# electrical_stuff_2_0.net
KiCad netlist of a schematic drawn in EAGLE
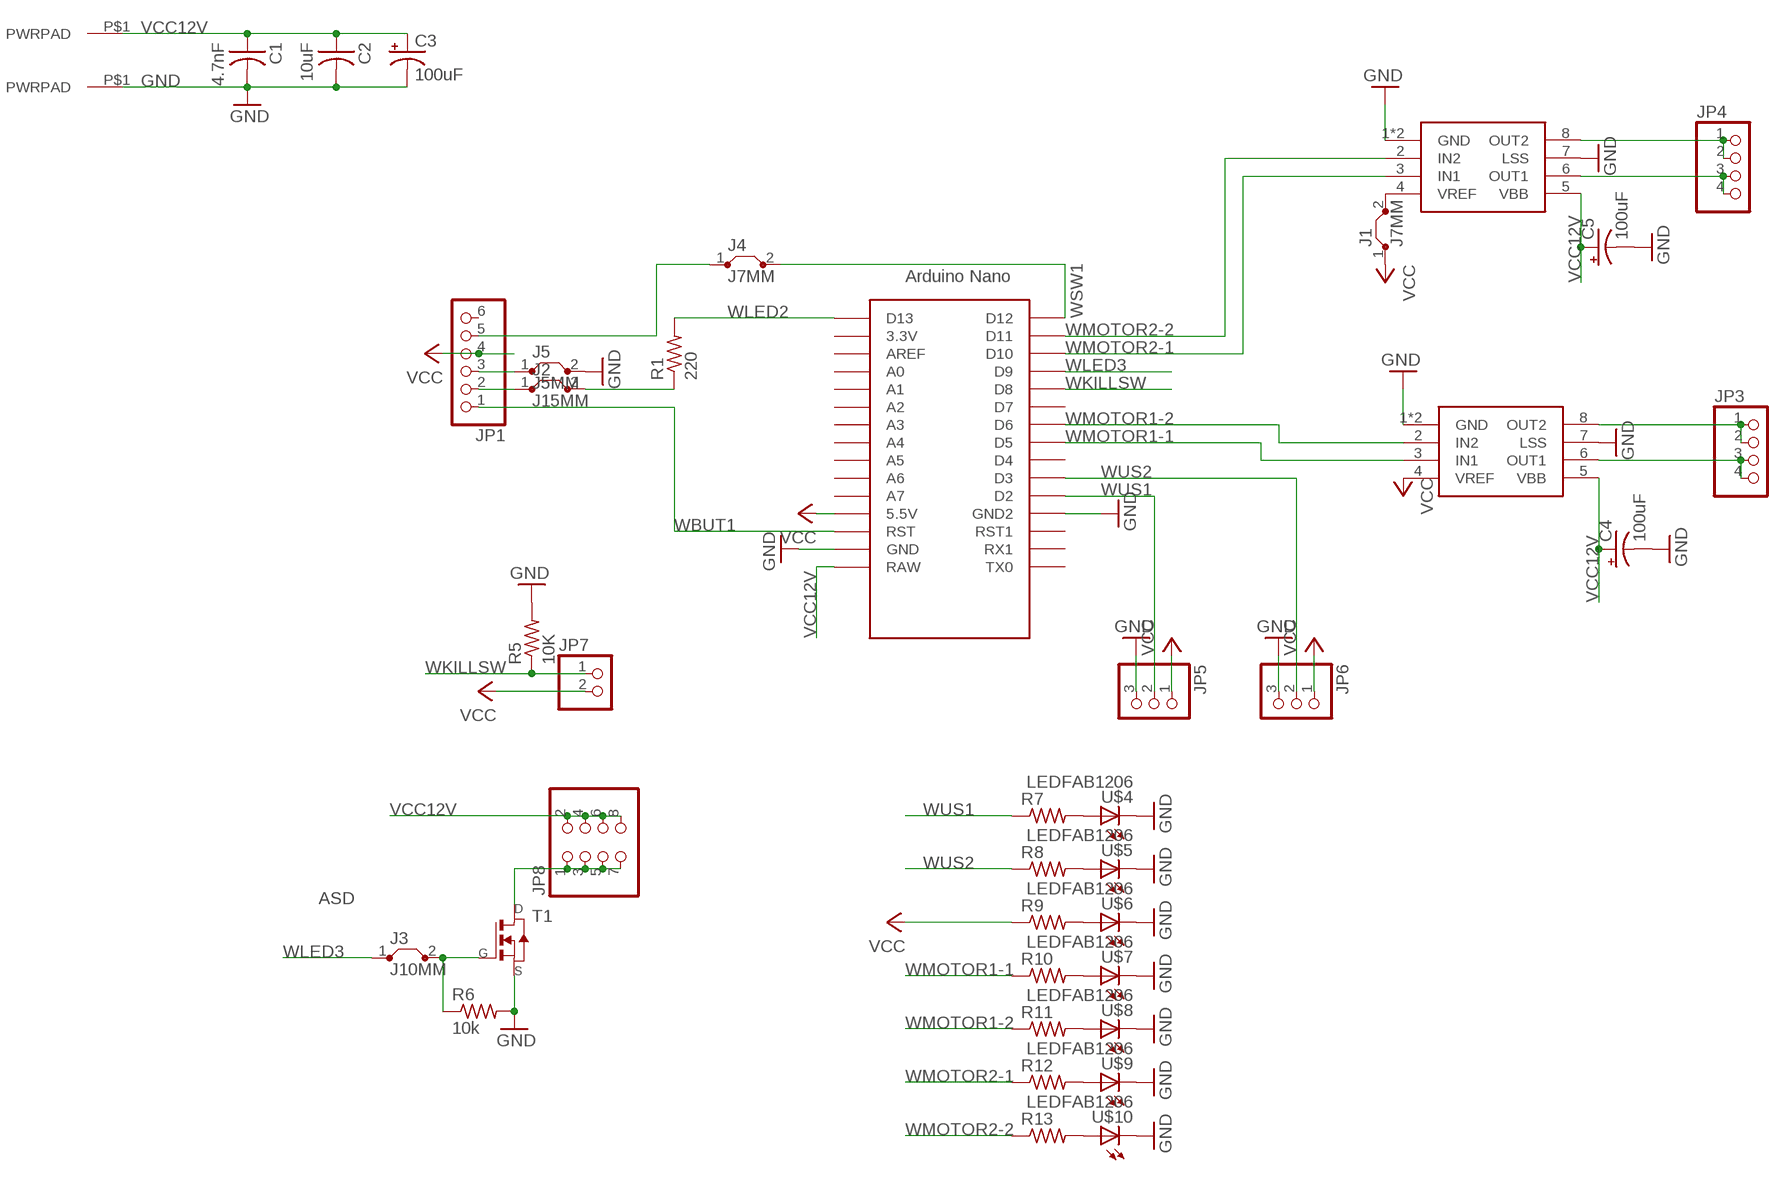
[diagram p0: schematic, sheet 1]

(export (version "E")
  (design (tool "Eeschema 10.0.6"))
  (components
    (comp (ref "C1")
      (value "4.7nF")
      (footprint "eagle-import:C1206FAB")
      (libsource (lib "eagle-import") (part "CAP-US1206FAB"))
    )
    (comp (ref "C2")
      (value "10uF")
      (footprint "eagle-import:C1206FAB")
      (libsource (lib "eagle-import") (part "CAP-US1206FAB"))
    )
    (comp (ref "C3")
      (value "100uF")
      (footprint "eagle-import:CPOL-RADIAL-2.5MM-6.5MM")
      (libsource (lib "eagle-import") (part "100UF-POLAR-RADIAL-2.5MM-25V-20%"))
    )
    (comp (ref "C4")
      (value "100uF")
      (footprint "eagle-import:CPOL-RADIAL-2.5MM-6.5MM")
      (libsource (lib "eagle-import") (part "100UF-POLAR-RADIAL-2.5MM-25V-20%"))
    )
    (comp (ref "C5")
      (value "100uF")
      (footprint "eagle-import:CPOL-RADIAL-2.5MM-6.5MM")
      (libsource (lib "eagle-import") (part "100UF-POLAR-RADIAL-2.5MM-25V-20%"))
    )
    (comp (ref "GND")
      (value "PWRPAD2-5MM")
      (footprint "eagle-import:PWRPAD_2-5MM")
      (libsource (lib "eagle-import") (part "PWRPAD2-5MM"))
    )
    (comp (ref "J1")
      (value "J7MM")
      (footprint "eagle-import:07")
      (libsource (lib "eagle-import") (part "J7MM"))
    )
    (comp (ref "J2")
      (value "J15MM")
      (footprint "eagle-import:15")
      (libsource (lib "eagle-import") (part "J15MM"))
    )
    (comp (ref "J3")
      (value "J10MM")
      (footprint "eagle-import:10")
      (libsource (lib "eagle-import") (part "J10MM"))
    )
    (comp (ref "J4")
      (value "J7MM")
      (footprint "eagle-import:07")
      (libsource (lib "eagle-import") (part "J7MM"))
    )
    (comp (ref "J5")
      (value "J5MM")
      (footprint "eagle-import:05")
      (libsource (lib "eagle-import") (part "J5MM"))
    )
    (comp (ref "JP1")
      (value "PINHD-1X6")
      (footprint "eagle-import:1X06")
      (libsource (lib "eagle-import") (part "PINHD-1X6"))
    )
    (comp (ref "JP3")
      (value "PINHD-1X4")
      (footprint "eagle-import:1X04")
      (libsource (lib "eagle-import") (part "PINHD-1X4"))
    )
    (comp (ref "JP4")
      (value "PINHD-1X4")
      (footprint "eagle-import:1X04")
      (libsource (lib "eagle-import") (part "PINHD-1X4"))
    )
    (comp (ref "JP5")
      (value "PINHD-1X3")
      (footprint "eagle-import:1X03")
      (libsource (lib "eagle-import") (part "PINHD-1X3"))
    )
    (comp (ref "JP6")
      (value "PINHD-1X3")
      (footprint "eagle-import:1X03")
      (libsource (lib "eagle-import") (part "PINHD-1X3"))
    )
    (comp (ref "JP7")
      (value "PINHD-1X2")
      (footprint "eagle-import:1X02")
      (libsource (lib "eagle-import") (part "PINHD-1X2"))
    )
    (comp (ref "JP8")
      (value "PINHD-2X4")
      (footprint "eagle-import:2X04")
      (libsource (lib "eagle-import") (part "PINHD-2X4"))
    )
    (comp (ref "R1")
      (value "220")
      (footprint "eagle-import:R1206FAB")
      (libsource (lib "eagle-import") (part "RES-US1206FAB"))
    )
    (comp (ref "R5")
      (value "10K")
      (footprint "eagle-import:R1206FAB")
      (libsource (lib "eagle-import") (part "RES-US1206FAB"))
    )
    (comp (ref "R6")
      (value "10k")
      (footprint "eagle-import:R1206FAB")
      (libsource (lib "eagle-import") (part "RES-US1206FAB"))
    )
    (comp (ref "R7")
      (value "RES-US1206FAB")
      (footprint "eagle-import:R1206FAB")
      (libsource (lib "eagle-import") (part "RES-US1206FAB"))
    )
    (comp (ref "R8")
      (value "RES-US1206FAB")
      (footprint "eagle-import:R1206FAB")
      (libsource (lib "eagle-import") (part "RES-US1206FAB"))
    )
    (comp (ref "R9")
      (value "RES-US1206FAB")
      (footprint "eagle-import:R1206FAB")
      (libsource (lib "eagle-import") (part "RES-US1206FAB"))
    )
    (comp (ref "R10")
      (value "RES-US1206FAB")
      (footprint "eagle-import:R1206FAB")
      (libsource (lib "eagle-import") (part "RES-US1206FAB"))
    )
    (comp (ref "R11")
      (value "RES-US1206FAB")
      (footprint "eagle-import:R1206FAB")
      (libsource (lib "eagle-import") (part "RES-US1206FAB"))
    )
    (comp (ref "R12")
      (value "RES-US1206FAB")
      (footprint "eagle-import:R1206FAB")
      (libsource (lib "eagle-import") (part "RES-US1206FAB"))
    )
    (comp (ref "R13")
      (value "RES-US1206FAB")
      (footprint "eagle-import:R1206FAB")
      (libsource (lib "eagle-import") (part "RES-US1206FAB"))
    )
    (comp (ref "T1")
      (value "NMOSFETTO252")
      (footprint "eagle-import:TO252")
      (libsource (lib "eagle-import") (part "NMOSFETTO252"))
    )
    (comp (ref "U$1")
      (value "NANO")
      (footprint "eagle-import:NANO")
      (libsource (lib "eagle-import") (part "NANO"))
    )
    (comp (ref "U$2")
      (value "A4953")
      (footprint "eagle-import:SOIC8_PAD")
      (libsource (lib "eagle-import") (part "A4953-H-BRIDGE-MOTOR-DRIVER-PAD"))
    )
    (comp (ref "U$3")
      (value "A4953")
      (footprint "eagle-import:SOIC8_PAD")
      (libsource (lib "eagle-import") (part "A4953-H-BRIDGE-MOTOR-DRIVER-PAD"))
    )
    (comp (ref "U$4")
      (value "LEDFAB1206")
      (footprint "eagle-import:LED1206FAB")
      (libsource (lib "eagle-import") (part "LEDFAB1206"))
    )
    (comp (ref "U$5")
      (value "LEDFAB1206")
      (footprint "eagle-import:LED1206FAB")
      (libsource (lib "eagle-import") (part "LEDFAB1206"))
    )
    (comp (ref "U$6")
      (value "LEDFAB1206")
      (footprint "eagle-import:LED1206FAB")
      (libsource (lib "eagle-import") (part "LEDFAB1206"))
    )
    (comp (ref "U$7")
      (value "LEDFAB1206")
      (footprint "eagle-import:LED1206FAB")
      (libsource (lib "eagle-import") (part "LEDFAB1206"))
    )
    (comp (ref "U$8")
      (value "LEDFAB1206")
      (footprint "eagle-import:LED1206FAB")
      (libsource (lib "eagle-import") (part "LEDFAB1206"))
    )
    (comp (ref "U$9")
      (value "LEDFAB1206")
      (footprint "eagle-import:LED1206FAB")
      (libsource (lib "eagle-import") (part "LEDFAB1206"))
    )
    (comp (ref "U$10")
      (value "LEDFAB1206")
      (footprint "eagle-import:LED1206FAB")
      (libsource (lib "eagle-import") (part "LEDFAB1206"))
    )
    (comp (ref "VCC12V")
      (value "VCC12V")
      (footprint "eagle-import:PWRPAD_2-5MM")
      (libsource (lib "eagle-import") (part "PWRPAD2-5MM"))
    )
  )
  (nets
    (net (code "1") (name "/ASD") (class "Default")
      (node (ref "J3") (pin "2") (pinfunction "2_2") (pintype "passive"))
      (node (ref "R6") (pin "1") (pinfunction "1_1") (pintype "passive"))
      (node (ref "T1") (pin "1") (pinfunction "G_1") (pintype "passive"))
    )
    (net (code "2") (name "/VCC12V") (class "Default")
      (node (ref "C1") (pin "1") (pinfunction "1_1") (pintype "passive"))
      (node (ref "C2") (pin "1") (pinfunction "1_1") (pintype "passive"))
      (node (ref "C3") (pin "1") (pinfunction "+_1") (pintype "passive"))
      (node (ref "C4") (pin "1") (pinfunction "+_1") (pintype "passive"))
      (node (ref "C5") (pin "1") (pinfunction "+_1") (pintype "passive"))
      (node (ref "JP8") (pin "2") (pinfunction "2_2") (pintype "passive"))
      (node (ref "JP8") (pin "4") (pinfunction "4_4") (pintype "passive"))
      (node (ref "JP8") (pin "6") (pinfunction "6_6") (pintype "passive"))
      (node (ref "JP8") (pin "8") (pinfunction "8_8") (pintype "passive"))
      (node (ref "U$1") (pin "RAW") (pinfunction "RAW_RAW") (pintype "bidirectional"))
      (node (ref "U$2") (pin "5") (pinfunction "VBB_5") (pintype "bidirectional"))
      (node (ref "U$3") (pin "5") (pinfunction "VBB_5") (pintype "bidirectional"))
      (node (ref "VCC12V") (pin "P$1") (pinfunction "PWRPAD_P$1") (pintype "bidirectional"))
    )
    (net (code "3") (name "/WBUT1") (class "Default")
      (node (ref "JP1") (pin "1") (pinfunction "1_1") (pintype "passive"))
      (node (ref "U$1") (pin "RST") (pinfunction "RST_RST") (pintype "bidirectional"))
    )
    (net (code "4") (name "/WKILLSW") (class "Default")
      (node (ref "JP7") (pin "1") (pinfunction "1_1") (pintype "passive"))
      (node (ref "R5") (pin "1") (pinfunction "1_1") (pintype "passive"))
      (node (ref "U$1") (pin "D8") (pinfunction "D8_D8") (pintype "bidirectional"))
    )
    (net (code "5") (name "/WLED2") (class "Default")
      (node (ref "R1") (pin "2") (pinfunction "2_2") (pintype "passive"))
      (node (ref "U$1") (pin "D13") (pinfunction "D13_D13") (pintype "bidirectional"))
    )
    (net (code "6") (name "/WLED3") (class "Default")
      (node (ref "J3") (pin "1") (pinfunction "1_1") (pintype "passive"))
      (node (ref "U$1") (pin "D9") (pinfunction "D9_D9") (pintype "bidirectional"))
    )
    (net (code "7") (name "/WMOTOR1-1") (class "Default")
      (node (ref "R10") (pin "1") (pinfunction "1_1") (pintype "passive"))
      (node (ref "U$1") (pin "D5") (pinfunction "D5_D5") (pintype "bidirectional"))
      (node (ref "U$2") (pin "3") (pinfunction "IN1_3") (pintype "bidirectional"))
    )
    (net (code "8") (name "/WMOTOR1-2") (class "Default")
      (node (ref "R11") (pin "1") (pinfunction "1_1") (pintype "passive"))
      (node (ref "U$1") (pin "D6") (pinfunction "D6_D6") (pintype "bidirectional"))
      (node (ref "U$2") (pin "2") (pinfunction "IN2_2") (pintype "bidirectional"))
    )
    (net (code "9") (name "/WMOTOR2-1") (class "Default")
      (node (ref "R12") (pin "1") (pinfunction "1_1") (pintype "passive"))
      (node (ref "U$1") (pin "D10") (pinfunction "D10_D10") (pintype "bidirectional"))
      (node (ref "U$3") (pin "3") (pinfunction "IN1_3") (pintype "bidirectional"))
    )
    (net (code "10") (name "/WMOTOR2-2") (class "Default")
      (node (ref "R13") (pin "1") (pinfunction "1_1") (pintype "passive"))
      (node (ref "U$1") (pin "D11") (pinfunction "D11_D11") (pintype "bidirectional"))
      (node (ref "U$3") (pin "2") (pinfunction "IN2_2") (pintype "bidirectional"))
    )
    (net (code "11") (name "/WSW1") (class "Default")
      (node (ref "J4") (pin "2") (pinfunction "2_2") (pintype "passive"))
      (node (ref "U$1") (pin "D12") (pinfunction "D12_D12") (pintype "bidirectional"))
    )
    (net (code "12") (name "/WUS1") (class "Default")
      (node (ref "JP5") (pin "2") (pinfunction "2_2") (pintype "passive"))
      (node (ref "R7") (pin "1") (pinfunction "1_1") (pintype "passive"))
      (node (ref "U$1") (pin "D2") (pinfunction "D2_D2") (pintype "bidirectional"))
    )
    (net (code "13") (name "/WUS2") (class "Default")
      (node (ref "JP6") (pin "2") (pinfunction "2_2") (pintype "passive"))
      (node (ref "R8") (pin "1") (pinfunction "1_1") (pintype "passive"))
      (node (ref "U$1") (pin "D3") (pinfunction "D3_D3") (pintype "bidirectional"))
    )
    (net (code "14") (name "GND") (class "Default")
      (node (ref "C1") (pin "2") (pinfunction "2_2") (pintype "passive"))
      (node (ref "C2") (pin "2") (pinfunction "2_2") (pintype "passive"))
      (node (ref "C3") (pin "2") (pinfunction "-_2") (pintype "passive"))
      (node (ref "C4") (pin "2") (pinfunction "-_2") (pintype "passive"))
      (node (ref "C5") (pin "2") (pinfunction "-_2") (pintype "passive"))
      (node (ref "GND") (pin "P$1") (pinfunction "PWRPAD_P$1") (pintype "bidirectional"))
      (node (ref "J5") (pin "2") (pinfunction "2_2") (pintype "passive"))
      (node (ref "JP5") (pin "3") (pinfunction "3_3") (pintype "passive"))
      (node (ref "JP6") (pin "3") (pinfunction "3_3") (pintype "passive"))
      (node (ref "R5") (pin "2") (pinfunction "2_2") (pintype "passive"))
      (node (ref "R6") (pin "2") (pinfunction "2_2") (pintype "passive"))
      (node (ref "T1") (pin "2") (pinfunction "S_2") (pintype "passive"))
      (node (ref "U$1") (pin "GND") (pinfunction "GND_GND") (pintype "bidirectional"))
      (node (ref "U$1") (pin "GND1") (pinfunction "GND2_GND1") (pintype "bidirectional"))
      (node (ref "U$10") (pin "2") (pinfunction "C_2") (pintype "passive"))
      (node (ref "U$2") (pin "1") (pinfunction "GND_1") (pintype "bidirectional"))
      (node (ref "U$2") (pin "7") (pinfunction "LSS_7") (pintype "bidirectional"))
      (node (ref "U$2") (pin "GND") (pinfunction "GND_GND") (pintype "bidirectional"))
      (node (ref "U$3") (pin "1") (pinfunction "GND_1") (pintype "bidirectional"))
      (node (ref "U$3") (pin "7") (pinfunction "LSS_7") (pintype "bidirectional"))
      (node (ref "U$3") (pin "GND") (pinfunction "GND_GND") (pintype "bidirectional"))
      (node (ref "U$4") (pin "2") (pinfunction "C_2") (pintype "passive"))
      (node (ref "U$5") (pin "2") (pinfunction "C_2") (pintype "passive"))
      (node (ref "U$6") (pin "2") (pinfunction "C_2") (pintype "passive"))
      (node (ref "U$7") (pin "2") (pinfunction "C_2") (pintype "passive"))
      (node (ref "U$8") (pin "2") (pinfunction "C_2") (pintype "passive"))
      (node (ref "U$9") (pin "2") (pinfunction "C_2") (pintype "passive"))
    )
    (net (code "15") (name "Net-(J2-Pad1)") (class "Default")
      (node (ref "J2") (pin "1") (pinfunction "1_1") (pintype "passive"))
      (node (ref "JP1") (pin "2") (pinfunction "2_2") (pintype "passive"))
    )
    (net (code "16") (name "Net-(J2-Pad2)") (class "Default")
      (node (ref "J2") (pin "2") (pinfunction "2_2") (pintype "passive"))
      (node (ref "R1") (pin "1") (pinfunction "1_1") (pintype "passive"))
    )
    (net (code "17") (name "Net-(J4-Pad1)") (class "Default")
      (node (ref "J4") (pin "1") (pinfunction "1_1") (pintype "passive"))
      (node (ref "JP1") (pin "5") (pinfunction "5_5") (pintype "passive"))
    )
    (net (code "18") (name "Net-(J5-Pad1)") (class "Default")
      (node (ref "J5") (pin "1") (pinfunction "1_1") (pintype "passive"))
      (node (ref "JP1") (pin "3") (pinfunction "3_3") (pintype "passive"))
    )
    (net (code "19") (name "Net-(T1-D)") (class "Default")
      (node (ref "JP8") (pin "1") (pinfunction "1_1") (pintype "passive"))
      (node (ref "JP8") (pin "3") (pinfunction "3_3") (pintype "passive"))
      (node (ref "JP8") (pin "5") (pinfunction "5_5") (pintype "passive"))
      (node (ref "JP8") (pin "7") (pinfunction "7_7") (pintype "passive"))
      (node (ref "T1") (pin "3") (pinfunction "D_3") (pintype "passive"))
    )
    (net (code "20") (name "Net-(U$2-OUT1)") (class "Default")
      (node (ref "JP3") (pin "3") (pinfunction "3_3") (pintype "passive"))
      (node (ref "JP3") (pin "4") (pinfunction "4_4") (pintype "passive"))
      (node (ref "U$2") (pin "6") (pinfunction "OUT1_6") (pintype "bidirectional"))
    )
    (net (code "21") (name "Net-(U$2-OUT2)") (class "Default")
      (node (ref "JP3") (pin "1") (pinfunction "1_1") (pintype "passive"))
      (node (ref "JP3") (pin "2") (pinfunction "2_2") (pintype "passive"))
      (node (ref "U$2") (pin "8") (pinfunction "OUT2_8") (pintype "bidirectional"))
    )
    (net (code "22") (name "Net-(U$3-OUT1)") (class "Default")
      (node (ref "JP4") (pin "3") (pinfunction "3_3") (pintype "passive"))
      (node (ref "JP4") (pin "4") (pinfunction "4_4") (pintype "passive"))
      (node (ref "U$3") (pin "6") (pinfunction "OUT1_6") (pintype "bidirectional"))
    )
    (net (code "23") (name "Net-(U$3-OUT2)") (class "Default")
      (node (ref "JP4") (pin "1") (pinfunction "1_1") (pintype "passive"))
      (node (ref "JP4") (pin "2") (pinfunction "2_2") (pintype "passive"))
      (node (ref "U$3") (pin "8") (pinfunction "OUT2_8") (pintype "bidirectional"))
    )
    (net (code "24") (name "Net-(U$3-VREF)") (class "Default")
      (node (ref "J1") (pin "2") (pinfunction "2_2") (pintype "passive"))
      (node (ref "U$3") (pin "4") (pinfunction "VREF_4") (pintype "bidirectional"))
    )
    (net (code "25") (name "Net-(U$4-A)") (class "Default")
      (node (ref "R7") (pin "2") (pinfunction "2_2") (pintype "passive"))
      (node (ref "U$4") (pin "1") (pinfunction "A_1") (pintype "passive"))
    )
    (net (code "26") (name "Net-(U$5-A)") (class "Default")
      (node (ref "R8") (pin "2") (pinfunction "2_2") (pintype "passive"))
      (node (ref "U$5") (pin "1") (pinfunction "A_1") (pintype "passive"))
    )
    (net (code "27") (name "Net-(U$6-A)") (class "Default")
      (node (ref "R9") (pin "2") (pinfunction "2_2") (pintype "passive"))
      (node (ref "U$6") (pin "1") (pinfunction "A_1") (pintype "passive"))
    )
    (net (code "28") (name "Net-(U$7-A)") (class "Default")
      (node (ref "R10") (pin "2") (pinfunction "2_2") (pintype "passive"))
      (node (ref "U$7") (pin "1") (pinfunction "A_1") (pintype "passive"))
    )
    (net (code "29") (name "Net-(U$8-A)") (class "Default")
      (node (ref "R11") (pin "2") (pinfunction "2_2") (pintype "passive"))
      (node (ref "U$8") (pin "1") (pinfunction "A_1") (pintype "passive"))
    )
    (net (code "30") (name "Net-(U$9-A)") (class "Default")
      (node (ref "R12") (pin "2") (pinfunction "2_2") (pintype "passive"))
      (node (ref "U$9") (pin "1") (pinfunction "A_1") (pintype "passive"))
    )
    (net (code "31") (name "Net-(U$10-A)") (class "Default")
      (node (ref "R13") (pin "2") (pinfunction "2_2") (pintype "passive"))
      (node (ref "U$10") (pin "1") (pinfunction "A_1") (pintype "passive"))
    )
    (net (code "32") (name "VCC") (class "Default")
      (node (ref "J1") (pin "1") (pinfunction "1_1") (pintype "passive"))
      (node (ref "JP1") (pin "4") (pinfunction "4_4") (pintype "passive"))
      (node (ref "JP5") (pin "1") (pinfunction "1_1") (pintype "passive"))
      (node (ref "JP6") (pin "1") (pinfunction "1_1") (pintype "passive"))
      (node (ref "JP7") (pin "2") (pinfunction "2_2") (pintype "passive"))
      (node (ref "R9") (pin "1") (pinfunction "1_1") (pintype "passive"))
      (node (ref "U$1") (pin "5V") (pinfunction "5.5V_5V") (pintype "bidirectional"))
      (node (ref "U$2") (pin "4") (pinfunction "VREF_4") (pintype "bidirectional"))
    )
    (net (code "33") (name "unconnected-(JP1-Pad6)") (class "Default")
      (node (ref "JP1") (pin "6") (pinfunction "6_6") (pintype "passive"))
    )
    (net (code "34") (name "unconnected-(U$1-Pad3.3V)") (class "Default")
      (node (ref "U$1") (pin "3.3V") (pinfunction "3.3V_3.3V") (pintype "bidirectional"))
    )
    (net (code "35") (name "unconnected-(U$1-PadA0)") (class "Default")
      (node (ref "U$1") (pin "A0") (pinfunction "A0_A0") (pintype "bidirectional"))
    )
    (net (code "36") (name "unconnected-(U$1-PadA1)") (class "Default")
      (node (ref "U$1") (pin "A1") (pinfunction "A1_A1") (pintype "bidirectional"))
    )
    (net (code "37") (name "unconnected-(U$1-PadA2)") (class "Default")
      (node (ref "U$1") (pin "A2") (pinfunction "A2_A2") (pintype "bidirectional"))
    )
    (net (code "38") (name "unconnected-(U$1-PadA3)") (class "Default")
      (node (ref "U$1") (pin "A3") (pinfunction "A3_A3") (pintype "bidirectional"))
    )
    (net (code "39") (name "unconnected-(U$1-PadA4)") (class "Default")
      (node (ref "U$1") (pin "A4") (pinfunction "A4_A4") (pintype "bidirectional"))
    )
    (net (code "40") (name "unconnected-(U$1-PadA5)") (class "Default")
      (node (ref "U$1") (pin "A5") (pinfunction "A5_A5") (pintype "bidirectional"))
    )
    (net (code "41") (name "unconnected-(U$1-PadA6)") (class "Default")
      (node (ref "U$1") (pin "A6") (pinfunction "A6_A6") (pintype "bidirectional"))
    )
    (net (code "42") (name "unconnected-(U$1-PadA7)") (class "Default")
      (node (ref "U$1") (pin "A7") (pinfunction "A7_A7") (pintype "bidirectional"))
    )
    (net (code "43") (name "unconnected-(U$1-PadAREF)") (class "Default")
      (node (ref "U$1") (pin "AREF") (pinfunction "AREF_AREF") (pintype "bidirectional"))
    )
    (net (code "44") (name "unconnected-(U$1-PadD4)") (class "Default")
      (node (ref "U$1") (pin "D4") (pinfunction "D4_D4") (pintype "bidirectional"))
    )
    (net (code "45") (name "unconnected-(U$1-PadD7)") (class "Default")
      (node (ref "U$1") (pin "D7") (pinfunction "D7_D7") (pintype "bidirectional"))
    )
    (net (code "46") (name "unconnected-(U$1-PadICSP1)") (class "Default")
      (node (ref "U$1") (pin "ICSP1") (pinfunction "ICSP1_ICSP1") (pintype "bidirectional"))
    )
    (net (code "47") (name "unconnected-(U$1-PadICSP2)") (class "Default")
      (node (ref "U$1") (pin "ICSP2") (pinfunction "ICSP2_ICSP2") (pintype "bidirectional"))
    )
    (net (code "48") (name "unconnected-(U$1-PadICSP3)") (class "Default")
      (node (ref "U$1") (pin "ICSP3") (pinfunction "ICSP3_ICSP3") (pintype "bidirectional"))
    )
    (net (code "49") (name "unconnected-(U$1-PadICSP4)") (class "Default")
      (node (ref "U$1") (pin "ICSP4") (pinfunction "ICSP4_ICSP4") (pintype "bidirectional"))
    )
    (net (code "50") (name "unconnected-(U$1-PadICSP5)") (class "Default")
      (node (ref "U$1") (pin "ICSP5") (pinfunction "ICSP5_ICSP5") (pintype "bidirectional"))
    )
    (net (code "51") (name "unconnected-(U$1-PadICSP6)") (class "Default")
      (node (ref "U$1") (pin "ICSP6") (pinfunction "ICSP6_ICSP6") (pintype "bidirectional"))
    )
    (net (code "52") (name "unconnected-(U$1-PadRST1)") (class "Default")
      (node (ref "U$1") (pin "RST1") (pinfunction "RST1_RST1") (pintype "bidirectional"))
    )
    (net (code "53") (name "unconnected-(U$1-PadRX1)") (class "Default")
      (node (ref "U$1") (pin "RX1") (pinfunction "RX1_RX1") (pintype "bidirectional"))
    )
    (net (code "54") (name "unconnected-(U$1-PadTX0)") (class "Default")
      (node (ref "U$1") (pin "TX0") (pinfunction "TX0_TX0") (pintype "bidirectional"))
    )
  )
)
